# Expand_Board.net
KiCad netlist of a schematic drawn in Altium Designer
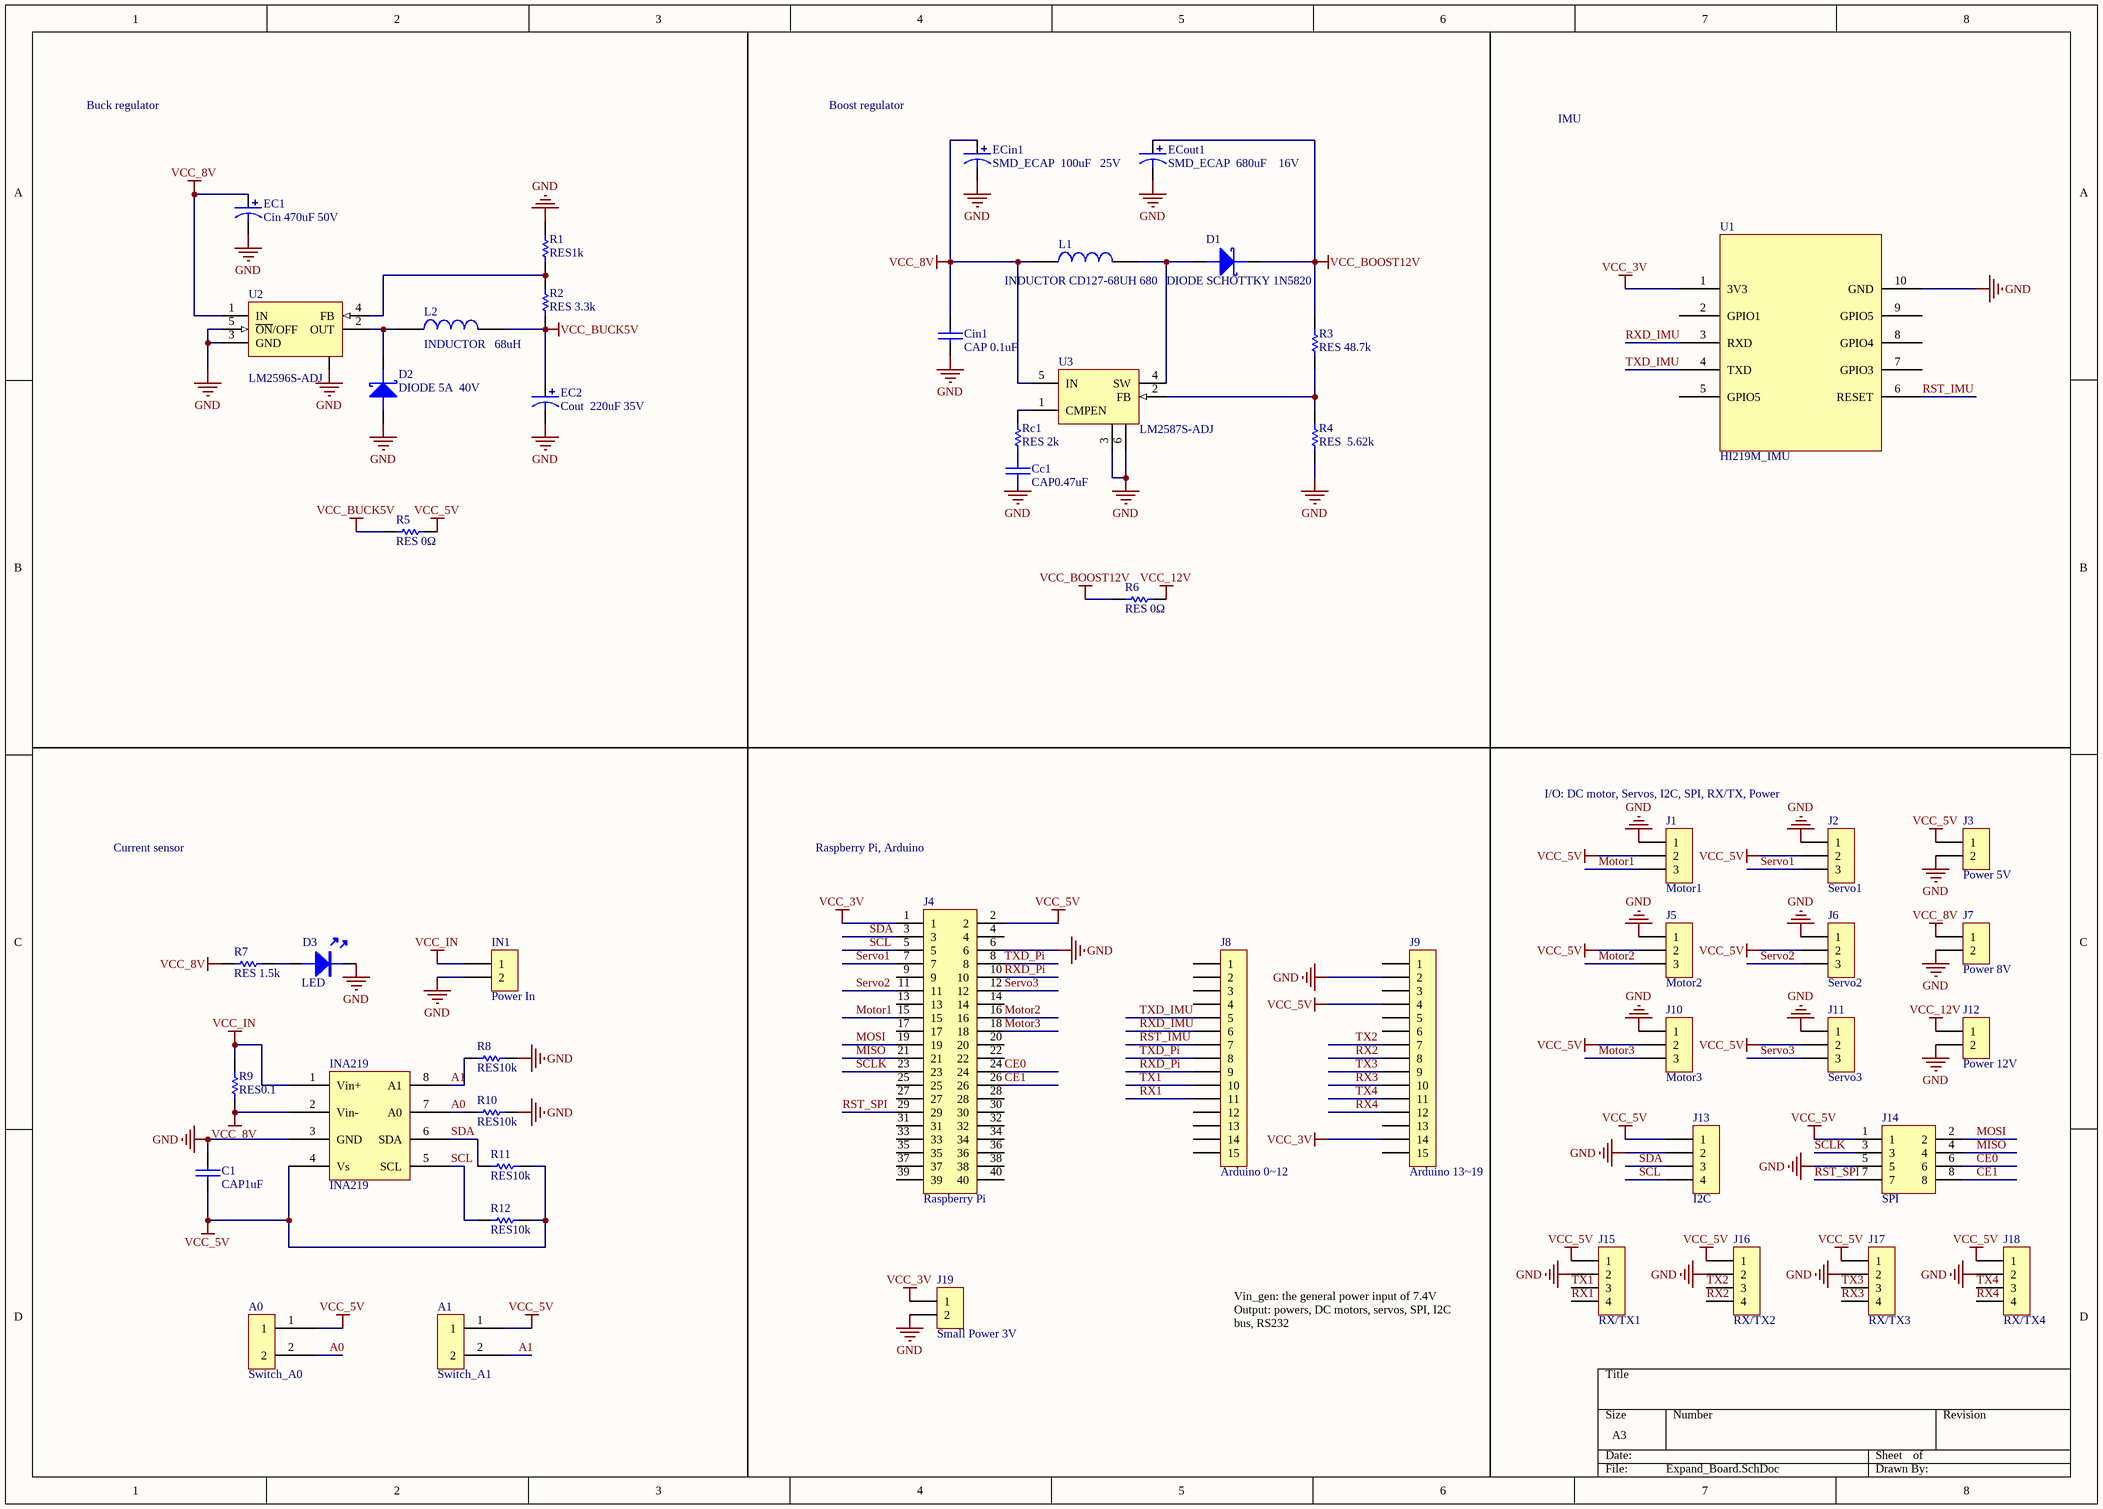
[diagram p0: Expand_Board.SchDoc]

(export (version "E")
  (design (tool "Eeschema 10.0.6"))
  (components
    (comp (ref "A0")
      (value "Switch_A0")
      (footprint "TSOP65P180X145-2N")
      (libsource (lib "Lianxin_Library") (part "Component_1"))
    )
    (comp (ref "A1")
      (value "Switch_A1")
      (footprint "TSOP65P180X145-2N")
      (libsource (lib "Lianxin_Library") (part "Component_1"))
    )
    (comp (ref "C1")
      (value "CAP1uF")
      (footprint "0603C")
      (description "无极性电容")
      (libsource (lib "电容") (part "CAP"))
    )
    (comp (ref "Cc1")
      (value "CAP0.47uF")
      (footprint "0805C")
      (description "无极性电容")
      (libsource (lib "电容") (part "CAP"))
    )
    (comp (ref "Cin1")
      (value "CAP 0.1uF")
      (footprint "0805C")
      (description "无极性电容")
      (libsource (lib "电容") (part "CAP"))
    )
    (comp (ref "D1")
      (value "DIODE SCHOTTKY 1N5820")
      (footprint "SMA/DO-214AC")
      (description "肖特基二极管")
      (libsource (lib "二极管") (part "DIODE SCHOTTKY"))
    )
    (comp (ref "D2")
      (value "DIODE 5A  40V")
      (footprint "SMA/DO-214AC")
      (description "肖特基二极管")
      (libsource (lib "二极管") (part "DIODE SCHOTTKY"))
    )
    (comp (ref "D3") (value "LED") (footprint "LED-0603B") (libsource (lib "LED") (part "LED")))
    (comp (ref "EC1")
      (value "Cin 470uF 50V")
      (footprint "SMD-EC8X8X10")
      (description "贴片电解电容")
      (libsource (lib "电容") (part "SMD_ECAP"))
    )
    (comp (ref "EC2")
      (value "Cout  220uF 35V")
      (footprint "SMD-EC8X8X10")
      (description "贴片电解电容")
      (libsource (lib "电容") (part "SMD_ECAP"))
    )
    (comp (ref "ECin1")
      (value "SMD_ECAP  100uF   25V")
      (footprint "SMD-EC8X8X10")
      (description "贴片电解电容")
      (libsource (lib "电容") (part "SMD_ECAP"))
    )
    (comp (ref "ECout1")
      (value "SMD_ECAP  680uF    16V")
      (footprint "SMD-EC8X8X10")
      (description "贴片电解电容")
      (libsource (lib "电容") (part "SMD_ECAP"))
    )
    (comp (ref "IN1")
      (value "Power In")
      (footprint "Pin HDR1X2/2.54mm-S")
      (libsource (lib "排针") (part "Pin HDR1X2"))
    )
    (comp (ref "INA219") (value "INA219") (footprint "INA219") (libsource (lib "INA219") (part "INA219")))
    (comp (ref "J1")
      (value "Motor1")
      (footprint "Pin HDR1X3/2.54mm-S")
      (libsource (lib "排针") (part "Pin HDR1X3"))
    )
    (comp (ref "J2")
      (value "Servo1")
      (footprint "Pin HDR1X3/2.54mm-S")
      (libsource (lib "排针") (part "Pin HDR1X3"))
    )
    (comp (ref "J3")
      (value "Power 5V")
      (footprint "Pin HDR1X2/2.54mm-S")
      (libsource (lib "排针") (part "Pin HDR1X2"))
    )
    (comp (ref "J4")
      (value "Raspberry Pi")
      (footprint "Pin HDR2X20/2.54mm-S")
      (libsource (lib "排针") (part "Pin HDR2X20"))
    )
    (comp (ref "J5")
      (value "Motor2")
      (footprint "Pin HDR1X3/2.54mm-S")
      (libsource (lib "排针") (part "Pin HDR1X3"))
    )
    (comp (ref "J6")
      (value "Servo2")
      (footprint "Pin HDR1X3/2.54mm-S")
      (libsource (lib "排针") (part "Pin HDR1X3"))
    )
    (comp (ref "J7")
      (value "Power 8V")
      (footprint "Pin HDR1X2/2.54mm-S")
      (libsource (lib "排针") (part "Pin HDR1X2"))
    )
    (comp (ref "J8")
      (value "Arduino 0~12")
      (footprint "Pin HDR1X15/2.54mm-S")
      (libsource (lib "排针") (part "Pin HDR1X15"))
    )
    (comp (ref "J9")
      (value "Arduino 13~19")
      (footprint "Pin HDR1X15/2.54mm-S")
      (libsource (lib "排针") (part "Pin HDR1X15"))
    )
    (comp (ref "J10")
      (value "Motor3")
      (footprint "Pin HDR1X3/2.54mm-S")
      (libsource (lib "排针") (part "Pin HDR1X3"))
    )
    (comp (ref "J11")
      (value "Servo3")
      (footprint "Pin HDR1X3/2.54mm-S")
      (libsource (lib "排针") (part "Pin HDR1X3"))
    )
    (comp (ref "J12")
      (value "Power 12V")
      (footprint "Pin HDR1X2/2.54mm-S")
      (libsource (lib "排针") (part "Pin HDR1X2"))
    )
    (comp (ref "J13")
      (value "I2C")
      (footprint "Pin HDR1X4/2.54mm-S")
      (libsource (lib "排针") (part "Pin HDR1X4"))
    )
    (comp (ref "J14")
      (value "SPI")
      (footprint "Pin HDR2X4/2.54mm-S")
      (libsource (lib "排针") (part "Pin HDR2X4"))
    )
    (comp (ref "J15")
      (value "RX/TX1")
      (footprint "Pin HDR1X4/2.54mm-S")
      (libsource (lib "排针") (part "Pin HDR1X4"))
    )
    (comp (ref "J16")
      (value "RX/TX2")
      (footprint "Pin HDR1X4/2.54mm-S")
      (libsource (lib "排针") (part "Pin HDR1X4"))
    )
    (comp (ref "J17")
      (value "RX/TX3")
      (footprint "Pin HDR1X4/2.54mm-S")
      (libsource (lib "排针") (part "Pin HDR1X4"))
    )
    (comp (ref "J18")
      (value "RX/TX4")
      (footprint "Pin HDR1X4/2.54mm-S")
      (libsource (lib "排针") (part "Pin HDR1X4"))
    )
    (comp (ref "J19")
      (value "Small Power 3V")
      (footprint "Pin HDR1X2/2.54mm-S")
      (libsource (lib "排针") (part "Pin HDR1X2"))
    )
    (comp (ref "L1")
      (value "INDUCTOR CD127-68UH 680")
      (footprint "CDRH127")
      (description "INDUCTOR")
      (libsource (lib "电感") (part "INDUCTOR"))
    )
    (comp (ref "L2")
      (value "INDUCTOR   68uH")
      (footprint "CDRH127")
      (description "INDUCTOR")
      (libsource (lib "电感") (part "INDUCTOR"))
    )
    (comp (ref "R1") (value "RES1k") (footprint "0603R") (libsource (lib "电阻") (part "RES")))
    (comp (ref "R2") (value "RES 3.3k") (footprint "0603R") (libsource (lib "电阻") (part "RES")))
    (comp (ref "R3") (value "RES 48.7k") (footprint "0603R") (libsource (lib "电阻") (part "RES")))
    (comp (ref "R4") (value "RES  5.62k") (footprint "0603R") (libsource (lib "电阻") (part "RES")))
    (comp (ref "R5") (value "RES 0Ω") (footprint "0603R") (libsource (lib "电阻") (part "RES")))
    (comp (ref "R6") (value "RES 0Ω") (footprint "0603R") (libsource (lib "电阻") (part "RES")))
    (comp (ref "R7") (value "RES 1.5k") (footprint "0603R") (libsource (lib "电阻") (part "RES")))
    (comp (ref "R8") (value "RES10k") (footprint "0603R") (libsource (lib "电阻") (part "RES")))
    (comp (ref "R9") (value "RES0.1") (footprint "2512R") (libsource (lib "电阻") (part "RES")))
    (comp (ref "R10") (value "RES10k") (footprint "0603R") (libsource (lib "电阻") (part "RES")))
    (comp (ref "R11") (value "RES10k") (footprint "0603R") (libsource (lib "电阻") (part "RES")))
    (comp (ref "R12") (value "RES10k") (footprint "0603R") (libsource (lib "电阻") (part "RES")))
    (comp (ref "Rc1") (value "RES 2k") (footprint "0603R") (libsource (lib "电阻") (part "RES")))
    (comp (ref "U1")
      (value "HI219M_IMU")
      (footprint "SON127P1220X265-10N")
      (libsource (lib "Hi219M_IMU_Lib") (part "Component_1"))
    )
    (comp (ref "U2")
      (value "LM2596S-ADJ")
      (footprint "TO-263-5")
      (description "可调稳压芯片")
      (fields (field (name "PUBLISHER") "Altium Limited"))
      (libsource (lib "fszhang") (part "LM2596S-ADJ"))
    )
    (comp (ref "U3")
      (value "LM2587S-ADJ")
      (footprint "TO-263-5")
      (description "DC升压")
      (fields (field (name "PUBLISHER") "Altium Limited"))
      (libsource (lib "fszhang") (part "LM2577S-ADJ"))
    )
  )
  (nets
    (net (code "1") (name "/A0") (class "Default")
      (node (ref "A0") (pin "2") (pinfunction "2_2") (pintype "passive"))
      (node (ref "INA219") (pin "7") (pinfunction "A0_7") (pintype "passive"))
      (node (ref "R10") (pin "1") (pinfunction "1_1") (pintype "passive"))
    )
    (net (code "2") (name "/A1") (class "Default")
      (node (ref "A1") (pin "2") (pinfunction "2_2") (pintype "passive"))
      (node (ref "INA219") (pin "8") (pinfunction "A1_8") (pintype "passive"))
      (node (ref "R8") (pin "1") (pinfunction "1_1") (pintype "passive"))
    )
    (net (code "3") (name "/CE0") (class "Default")
      (node (ref "J14") (pin "6") (pinfunction "6_6") (pintype "passive"))
      (node (ref "J4") (pin "24") (pinfunction "24_24") (pintype "passive"))
    )
    (net (code "4") (name "/CE1") (class "Default")
      (node (ref "J14") (pin "8") (pinfunction "8_8") (pintype "passive"))
      (node (ref "J4") (pin "26") (pinfunction "26_26") (pintype "passive"))
    )
    (net (code "5") (name "/MISO") (class "Default")
      (node (ref "J14") (pin "4") (pinfunction "4_4") (pintype "passive"))
      (node (ref "J4") (pin "21") (pinfunction "21_21") (pintype "passive"))
    )
    (net (code "6") (name "/MOSI") (class "Default")
      (node (ref "J14") (pin "2") (pinfunction "2_2") (pintype "passive"))
      (node (ref "J4") (pin "19") (pinfunction "19_19") (pintype "passive"))
    )
    (net (code "7") (name "/Motor1") (class "Default")
      (node (ref "J1") (pin "3") (pinfunction "3_3") (pintype "passive"))
      (node (ref "J4") (pin "15") (pinfunction "15_15") (pintype "passive"))
    )
    (net (code "8") (name "/Motor2") (class "Default")
      (node (ref "J4") (pin "16") (pinfunction "16_16") (pintype "passive"))
      (node (ref "J5") (pin "3") (pinfunction "3_3") (pintype "passive"))
    )
    (net (code "9") (name "/Motor3") (class "Default")
      (node (ref "J10") (pin "3") (pinfunction "3_3") (pintype "passive"))
      (node (ref "J4") (pin "18") (pinfunction "18_18") (pintype "passive"))
    )
    (net (code "10") (name "/RST_IMU") (class "Default")
      (node (ref "J8") (pin "7") (pinfunction "7_7") (pintype "passive"))
      (node (ref "U1") (pin "6") (pinfunction "RESET_6") (pintype "passive"))
    )
    (net (code "11") (name "/RST_SPI") (class "Default")
      (node (ref "J14") (pin "7") (pinfunction "7_7") (pintype "passive"))
      (node (ref "J4") (pin "29") (pinfunction "29_29") (pintype "passive"))
    )
    (net (code "12") (name "/RX1") (class "Default")
      (node (ref "J15") (pin "4") (pinfunction "4_4") (pintype "passive"))
      (node (ref "J8") (pin "11") (pinfunction "11_11") (pintype "passive"))
    )
    (net (code "13") (name "/RX2") (class "Default")
      (node (ref "J16") (pin "4") (pinfunction "4_4") (pintype "passive"))
      (node (ref "J9") (pin "8") (pinfunction "8_8") (pintype "passive"))
    )
    (net (code "14") (name "/RX3") (class "Default")
      (node (ref "J17") (pin "4") (pinfunction "4_4") (pintype "passive"))
      (node (ref "J9") (pin "10") (pinfunction "10_10") (pintype "passive"))
    )
    (net (code "15") (name "/RX4") (class "Default")
      (node (ref "J18") (pin "4") (pinfunction "4_4") (pintype "passive"))
      (node (ref "J9") (pin "12") (pinfunction "12_12") (pintype "passive"))
    )
    (net (code "16") (name "/RXD_IMU") (class "Default")
      (node (ref "J8") (pin "6") (pinfunction "6_6") (pintype "passive"))
      (node (ref "U1") (pin "3") (pinfunction "RXD_3") (pintype "passive"))
    )
    (net (code "17") (name "/RXD_Pi") (class "Default")
      (node (ref "J4") (pin "10") (pinfunction "10_10") (pintype "passive"))
      (node (ref "J8") (pin "9") (pinfunction "9_9") (pintype "passive"))
    )
    (net (code "18") (name "/SCL") (class "Default")
      (node (ref "INA219") (pin "5") (pinfunction "SCL_5") (pintype "passive"))
      (node (ref "J13") (pin "4") (pinfunction "4_4") (pintype "passive"))
      (node (ref "J4") (pin "5") (pinfunction "5_5") (pintype "passive"))
      (node (ref "R12") (pin "1") (pinfunction "1_1") (pintype "passive"))
    )
    (net (code "19") (name "/SCLK") (class "Default")
      (node (ref "J14") (pin "3") (pinfunction "3_3") (pintype "passive"))
      (node (ref "J4") (pin "23") (pinfunction "23_23") (pintype "passive"))
    )
    (net (code "20") (name "/SDA") (class "Default")
      (node (ref "INA219") (pin "6") (pinfunction "SDA_6") (pintype "passive"))
      (node (ref "J13") (pin "3") (pinfunction "3_3") (pintype "passive"))
      (node (ref "J4") (pin "3") (pinfunction "3_3") (pintype "passive"))
      (node (ref "R11") (pin "1") (pinfunction "1_1") (pintype "passive"))
    )
    (net (code "21") (name "/Servo1") (class "Default")
      (node (ref "J2") (pin "3") (pinfunction "3_3") (pintype "passive"))
      (node (ref "J4") (pin "7") (pinfunction "7_7") (pintype "passive"))
    )
    (net (code "22") (name "/Servo2") (class "Default")
      (node (ref "J4") (pin "11") (pinfunction "11_11") (pintype "passive"))
      (node (ref "J6") (pin "3") (pinfunction "3_3") (pintype "passive"))
    )
    (net (code "23") (name "/Servo3") (class "Default")
      (node (ref "J11") (pin "3") (pinfunction "3_3") (pintype "passive"))
      (node (ref "J4") (pin "12") (pinfunction "12_12") (pintype "passive"))
    )
    (net (code "24") (name "/TX1") (class "Default")
      (node (ref "J15") (pin "3") (pinfunction "3_3") (pintype "passive"))
      (node (ref "J8") (pin "10") (pinfunction "10_10") (pintype "passive"))
    )
    (net (code "25") (name "/TX2") (class "Default")
      (node (ref "J16") (pin "3") (pinfunction "3_3") (pintype "passive"))
      (node (ref "J9") (pin "7") (pinfunction "7_7") (pintype "passive"))
    )
    (net (code "26") (name "/TX3") (class "Default")
      (node (ref "J17") (pin "3") (pinfunction "3_3") (pintype "passive"))
      (node (ref "J9") (pin "9") (pinfunction "9_9") (pintype "passive"))
    )
    (net (code "27") (name "/TX4") (class "Default")
      (node (ref "J18") (pin "3") (pinfunction "3_3") (pintype "passive"))
      (node (ref "J9") (pin "11") (pinfunction "11_11") (pintype "passive"))
    )
    (net (code "28") (name "/TXD_IMU") (class "Default")
      (node (ref "J8") (pin "5") (pinfunction "5_5") (pintype "passive"))
      (node (ref "U1") (pin "4") (pinfunction "TXD_4") (pintype "passive"))
    )
    (net (code "29") (name "/TXD_Pi") (class "Default")
      (node (ref "J4") (pin "8") (pinfunction "8_8") (pintype "passive"))
      (node (ref "J8") (pin "8") (pinfunction "8_8") (pintype "passive"))
    )
    (net (code "30") (name "GND") (class "Default")
      (node (ref "C1") (pin "2") (pinfunction "2_2") (pintype "passive"))
      (node (ref "Cc1") (pin "1") (pinfunction "1_1") (pintype "passive"))
      (node (ref "Cin1") (pin "1") (pinfunction "1_1") (pintype "passive"))
      (node (ref "D2") (pin "A") (pinfunction "A_A") (pintype "passive"))
      (node (ref "D3") (pin "K") (pinfunction "K_K") (pintype "passive"))
      (node (ref "EC1") (pin "2") (pinfunction "2_2") (pintype "passive"))
      (node (ref "EC2") (pin "2") (pinfunction "2_2") (pintype "passive"))
      (node (ref "ECin1") (pin "2") (pinfunction "2_2") (pintype "passive"))
      (node (ref "ECout1") (pin "2") (pinfunction "2_2") (pintype "passive"))
      (node (ref "IN1") (pin "2") (pinfunction "2_2") (pintype "passive"))
      (node (ref "INA219") (pin "3") (pinfunction "GND_3") (pintype "passive"))
      (node (ref "J1") (pin "1") (pinfunction "1_1") (pintype "passive"))
      (node (ref "J10") (pin "1") (pinfunction "1_1") (pintype "passive"))
      (node (ref "J11") (pin "1") (pinfunction "1_1") (pintype "passive"))
      (node (ref "J12") (pin "2") (pinfunction "2_2") (pintype "passive"))
      (node (ref "J13") (pin "2") (pinfunction "2_2") (pintype "passive"))
      (node (ref "J14") (pin "5") (pinfunction "5_5") (pintype "passive"))
      (node (ref "J15") (pin "2") (pinfunction "2_2") (pintype "passive"))
      (node (ref "J16") (pin "2") (pinfunction "2_2") (pintype "passive"))
      (node (ref "J17") (pin "2") (pinfunction "2_2") (pintype "passive"))
      (node (ref "J18") (pin "2") (pinfunction "2_2") (pintype "passive"))
      (node (ref "J19") (pin "2") (pinfunction "2_2") (pintype "passive"))
      (node (ref "J2") (pin "1") (pinfunction "1_1") (pintype "passive"))
      (node (ref "J3") (pin "2") (pinfunction "2_2") (pintype "passive"))
      (node (ref "J4") (pin "6") (pinfunction "6_6") (pintype "passive"))
      (node (ref "J5") (pin "1") (pinfunction "1_1") (pintype "passive"))
      (node (ref "J6") (pin "1") (pinfunction "1_1") (pintype "passive"))
      (node (ref "J7") (pin "2") (pinfunction "2_2") (pintype "passive"))
      (node (ref "J9") (pin "2") (pinfunction "2_2") (pintype "passive"))
      (node (ref "R1") (pin "2") (pinfunction "2_2") (pintype "passive"))
      (node (ref "R10") (pin "2") (pinfunction "2_2") (pintype "passive"))
      (node (ref "R4") (pin "1") (pinfunction "1_1") (pintype "passive"))
      (node (ref "R8") (pin "2") (pinfunction "2_2") (pintype "passive"))
      (node (ref "U1") (pin "10") (pinfunction "GND_10") (pintype "passive"))
      (node (ref "U2") (pin "3") (pinfunction "GND_3") (pintype "power_in"))
      (node (ref "U2") (pin "5") (pinfunction "~{ON}/OFF_5") (pintype "input"))
      (node (ref "U2") (pin "6") (pinfunction "6_6") (pintype "power_in"))
      (node (ref "U3") (pin "3") (pinfunction "GND_3") (pintype "power_in"))
      (node (ref "U3") (pin "6") (pinfunction "6_6") (pintype "passive"))
    )
    (net (code "31") (name "Net-(Cc1-Pad2)") (class "Default")
      (node (ref "Cc1") (pin "2") (pinfunction "2_2") (pintype "passive"))
      (node (ref "Rc1") (pin "1") (pinfunction "1_1") (pintype "passive"))
    )
    (net (code "32") (name "Net-(D3-PadA)") (class "Default")
      (node (ref "D3") (pin "A") (pinfunction "A_A") (pintype "passive"))
      (node (ref "R7") (pin "1") (pinfunction "1_1") (pintype "passive"))
    )
    (net (code "33") (name "Net-(U2-FB)") (class "Default")
      (node (ref "R1") (pin "1") (pinfunction "1_1") (pintype "passive"))
      (node (ref "R2") (pin "2") (pinfunction "2_2") (pintype "passive"))
      (node (ref "U2") (pin "4") (pinfunction "FB_4") (pintype "input"))
    )
    (net (code "34") (name "Net-(U2-OUT)") (class "Default")
      (node (ref "D2") (pin "K") (pinfunction "K_K") (pintype "passive"))
      (node (ref "L2") (pin "1") (pinfunction "1_1") (pintype "passive"))
      (node (ref "U2") (pin "2") (pinfunction "OUT_2") (pintype "power_in"))
    )
    (net (code "35") (name "Net-(U3-CMPEN)") (class "Default")
      (node (ref "Rc1") (pin "2") (pinfunction "2_2") (pintype "passive"))
      (node (ref "U3") (pin "1") (pinfunction "CMPEN_1") (pintype "passive"))
    )
    (net (code "36") (name "Net-(U3-FB)") (class "Default")
      (node (ref "R3") (pin "1") (pinfunction "1_1") (pintype "passive"))
      (node (ref "R4") (pin "2") (pinfunction "2_2") (pintype "passive"))
      (node (ref "U3") (pin "2") (pinfunction "FB_2") (pintype "input"))
    )
    (net (code "37") (name "Net-(U3-SW)") (class "Default")
      (node (ref "D1") (pin "A") (pinfunction "A_A") (pintype "passive"))
      (node (ref "L1") (pin "2") (pinfunction "2_2") (pintype "passive"))
      (node (ref "U3") (pin "4") (pinfunction "SW_4") (pintype "power_in"))
    )
    (net (code "38") (name "VCC_3V") (class "Default")
      (node (ref "J19") (pin "1") (pinfunction "1_1") (pintype "passive"))
      (node (ref "J4") (pin "1") (pinfunction "1_1") (pintype "passive"))
      (node (ref "J9") (pin "14") (pinfunction "14_14") (pintype "passive"))
      (node (ref "U1") (pin "1") (pinfunction "3V3_1") (pintype "passive"))
    )
    (net (code "39") (name "VCC_5V") (class "Default")
      (node (ref "A0") (pin "1") (pinfunction "1_1") (pintype "passive"))
      (node (ref "A1") (pin "1") (pinfunction "1_1") (pintype "passive"))
      (node (ref "C1") (pin "1") (pinfunction "1_1") (pintype "passive"))
      (node (ref "INA219") (pin "4") (pinfunction "Vs_4") (pintype "passive"))
      (node (ref "J1") (pin "2") (pinfunction "2_2") (pintype "passive"))
      (node (ref "J10") (pin "2") (pinfunction "2_2") (pintype "passive"))
      (node (ref "J11") (pin "2") (pinfunction "2_2") (pintype "passive"))
      (node (ref "J13") (pin "1") (pinfunction "1_1") (pintype "passive"))
      (node (ref "J14") (pin "1") (pinfunction "1_1") (pintype "passive"))
      (node (ref "J15") (pin "1") (pinfunction "1_1") (pintype "passive"))
      (node (ref "J16") (pin "1") (pinfunction "1_1") (pintype "passive"))
      (node (ref "J17") (pin "1") (pinfunction "1_1") (pintype "passive"))
      (node (ref "J18") (pin "1") (pinfunction "1_1") (pintype "passive"))
      (node (ref "J2") (pin "2") (pinfunction "2_2") (pintype "passive"))
      (node (ref "J3") (pin "1") (pinfunction "1_1") (pintype "passive"))
      (node (ref "J4") (pin "2") (pinfunction "2_2") (pintype "passive"))
      (node (ref "J5") (pin "2") (pinfunction "2_2") (pintype "passive"))
      (node (ref "J6") (pin "2") (pinfunction "2_2") (pintype "passive"))
      (node (ref "J9") (pin "4") (pinfunction "4_4") (pintype "passive"))
      (node (ref "R11") (pin "2") (pinfunction "2_2") (pintype "passive"))
      (node (ref "R12") (pin "2") (pinfunction "2_2") (pintype "passive"))
      (node (ref "R5") (pin "2") (pinfunction "2_2") (pintype "passive"))
    )
    (net (code "40") (name "VCC_8V") (class "Default")
      (node (ref "Cin1") (pin "2") (pinfunction "2_2") (pintype "passive"))
      (node (ref "EC1") (pin "1") (pinfunction "1_1") (pintype "passive"))
      (node (ref "ECin1") (pin "1") (pinfunction "1_1") (pintype "passive"))
      (node (ref "INA219") (pin "2") (pinfunction "Vin-_2") (pintype "passive"))
      (node (ref "J7") (pin "1") (pinfunction "1_1") (pintype "passive"))
      (node (ref "L1") (pin "1") (pinfunction "1_1") (pintype "passive"))
      (node (ref "R7") (pin "2") (pinfunction "2_2") (pintype "passive"))
      (node (ref "R9") (pin "2") (pinfunction "2_2") (pintype "passive"))
      (node (ref "U2") (pin "1") (pinfunction "IN_1") (pintype "power_in"))
      (node (ref "U3") (pin "5") (pinfunction "IN_5") (pintype "power_in"))
    )
    (net (code "41") (name "VCC_12V") (class "Default")
      (node (ref "J12") (pin "1") (pinfunction "1_1") (pintype "passive"))
      (node (ref "R6") (pin "2") (pinfunction "2_2") (pintype "passive"))
    )
    (net (code "42") (name "VCC_BOOST12V") (class "Default")
      (node (ref "D1") (pin "K") (pinfunction "K_K") (pintype "passive"))
      (node (ref "ECout1") (pin "1") (pinfunction "1_1") (pintype "passive"))
      (node (ref "R3") (pin "2") (pinfunction "2_2") (pintype "passive"))
      (node (ref "R6") (pin "1") (pinfunction "1_1") (pintype "passive"))
    )
    (net (code "43") (name "VCC_BUCK5V") (class "Default")
      (node (ref "EC2") (pin "1") (pinfunction "1_1") (pintype "passive"))
      (node (ref "L2") (pin "2") (pinfunction "2_2") (pintype "passive"))
      (node (ref "R2") (pin "1") (pinfunction "1_1") (pintype "passive"))
      (node (ref "R5") (pin "1") (pinfunction "1_1") (pintype "passive"))
    )
    (net (code "44") (name "VCC_IN") (class "Default")
      (node (ref "IN1") (pin "1") (pinfunction "1_1") (pintype "passive"))
      (node (ref "INA219") (pin "1") (pinfunction "Vin+_1") (pintype "passive"))
      (node (ref "R9") (pin "1") (pinfunction "1_1") (pintype "passive"))
    )
    (net (code "45") (name "unconnected-(J4-Pad4)") (class "Default")
      (node (ref "J4") (pin "4") (pinfunction "4_4") (pintype "passive"))
    )
    (net (code "46") (name "unconnected-(J4-Pad9)") (class "Default")
      (node (ref "J4") (pin "9") (pinfunction "9_9") (pintype "passive"))
    )
    (net (code "47") (name "unconnected-(J4-Pad13)") (class "Default")
      (node (ref "J4") (pin "13") (pinfunction "13_13") (pintype "passive"))
    )
    (net (code "48") (name "unconnected-(J4-Pad14)") (class "Default")
      (node (ref "J4") (pin "14") (pinfunction "14_14") (pintype "passive"))
    )
    (net (code "49") (name "unconnected-(J4-Pad17)") (class "Default")
      (node (ref "J4") (pin "17") (pinfunction "17_17") (pintype "passive"))
    )
    (net (code "50") (name "unconnected-(J4-Pad20)") (class "Default")
      (node (ref "J4") (pin "20") (pinfunction "20_20") (pintype "passive"))
    )
    (net (code "51") (name "unconnected-(J4-Pad22)") (class "Default")
      (node (ref "J4") (pin "22") (pinfunction "22_22") (pintype "passive"))
    )
    (net (code "52") (name "unconnected-(J4-Pad25)") (class "Default")
      (node (ref "J4") (pin "25") (pinfunction "25_25") (pintype "passive"))
    )
    (net (code "53") (name "unconnected-(J4-Pad27)") (class "Default")
      (node (ref "J4") (pin "27") (pinfunction "27_27") (pintype "passive"))
    )
    (net (code "54") (name "unconnected-(J4-Pad28)") (class "Default")
      (node (ref "J4") (pin "28") (pinfunction "28_28") (pintype "passive"))
    )
    (net (code "55") (name "unconnected-(J4-Pad30)") (class "Default")
      (node (ref "J4") (pin "30") (pinfunction "30_30") (pintype "passive"))
    )
    (net (code "56") (name "unconnected-(J4-Pad31)") (class "Default")
      (node (ref "J4") (pin "31") (pinfunction "31_31") (pintype "passive"))
    )
    (net (code "57") (name "unconnected-(J4-Pad32)") (class "Default")
      (node (ref "J4") (pin "32") (pinfunction "32_32") (pintype "passive"))
    )
    (net (code "58") (name "unconnected-(J4-Pad33)") (class "Default")
      (node (ref "J4") (pin "33") (pinfunction "33_33") (pintype "passive"))
    )
    (net (code "59") (name "unconnected-(J4-Pad34)") (class "Default")
      (node (ref "J4") (pin "34") (pinfunction "34_34") (pintype "passive"))
    )
    (net (code "60") (name "unconnected-(J4-Pad35)") (class "Default")
      (node (ref "J4") (pin "35") (pinfunction "35_35") (pintype "passive"))
    )
    (net (code "61") (name "unconnected-(J4-Pad36)") (class "Default")
      (node (ref "J4") (pin "36") (pinfunction "36_36") (pintype "passive"))
    )
    (net (code "62") (name "unconnected-(J4-Pad37)") (class "Default")
      (node (ref "J4") (pin "37") (pinfunction "37_37") (pintype "passive"))
    )
    (net (code "63") (name "unconnected-(J4-Pad38)") (class "Default")
      (node (ref "J4") (pin "38") (pinfunction "38_38") (pintype "passive"))
    )
    (net (code "64") (name "unconnected-(J4-Pad39)") (class "Default")
      (node (ref "J4") (pin "39") (pinfunction "39_39") (pintype "passive"))
    )
    (net (code "65") (name "unconnected-(J4-Pad40)") (class "Default")
      (node (ref "J4") (pin "40") (pinfunction "40_40") (pintype "passive"))
    )
    (net (code "66") (name "unconnected-(J8-Pad1)") (class "Default")
      (node (ref "J8") (pin "1") (pinfunction "1_1") (pintype "passive"))
    )
    (net (code "67") (name "unconnected-(J8-Pad2)") (class "Default")
      (node (ref "J8") (pin "2") (pinfunction "2_2") (pintype "passive"))
    )
    (net (code "68") (name "unconnected-(J8-Pad3)") (class "Default")
      (node (ref "J8") (pin "3") (pinfunction "3_3") (pintype "passive"))
    )
    (net (code "69") (name "unconnected-(J8-Pad4)") (class "Default")
      (node (ref "J8") (pin "4") (pinfunction "4_4") (pintype "passive"))
    )
    (net (code "70") (name "unconnected-(J8-Pad12)") (class "Default")
      (node (ref "J8") (pin "12") (pinfunction "12_12") (pintype "passive"))
    )
    (net (code "71") (name "unconnected-(J8-Pad13)") (class "Default")
      (node (ref "J8") (pin "13") (pinfunction "13_13") (pintype "passive"))
    )
    (net (code "72") (name "unconnected-(J8-Pad14)") (class "Default")
      (node (ref "J8") (pin "14") (pinfunction "14_14") (pintype "passive"))
    )
    (net (code "73") (name "unconnected-(J8-Pad15)") (class "Default")
      (node (ref "J8") (pin "15") (pinfunction "15_15") (pintype "passive"))
    )
    (net (code "74") (name "unconnected-(J9-Pad1)") (class "Default")
      (node (ref "J9") (pin "1") (pinfunction "1_1") (pintype "passive"))
    )
    (net (code "75") (name "unconnected-(J9-Pad3)") (class "Default")
      (node (ref "J9") (pin "3") (pinfunction "3_3") (pintype "passive"))
    )
    (net (code "76") (name "unconnected-(J9-Pad5)") (class "Default")
      (node (ref "J9") (pin "5") (pinfunction "5_5") (pintype "passive"))
    )
    (net (code "77") (name "unconnected-(J9-Pad6)") (class "Default")
      (node (ref "J9") (pin "6") (pinfunction "6_6") (pintype "passive"))
    )
    (net (code "78") (name "unconnected-(J9-Pad13)") (class "Default")
      (node (ref "J9") (pin "13") (pinfunction "13_13") (pintype "passive"))
    )
    (net (code "79") (name "unconnected-(J9-Pad15)") (class "Default")
      (node (ref "J9") (pin "15") (pinfunction "15_15") (pintype "passive"))
    )
    (net (code "80") (name "unconnected-(U1-GPIO1-Pad2)") (class "Default")
      (node (ref "U1") (pin "2") (pinfunction "GPIO1_2") (pintype "passive"))
    )
    (net (code "81") (name "unconnected-(U1-GPIO3-Pad7)") (class "Default")
      (node (ref "U1") (pin "7") (pinfunction "GPIO3_7") (pintype "passive"))
    )
    (net (code "82") (name "unconnected-(U1-GPIO4-Pad8)") (class "Default")
      (node (ref "U1") (pin "8") (pinfunction "GPIO4_8") (pintype "passive"))
    )
    (net (code "83") (name "unconnected-(U1-GPIO5-Pad5)") (class "Default")
      (node (ref "U1") (pin "5") (pinfunction "GPIO5_5") (pintype "passive"))
    )
    (net (code "84") (name "unconnected-(U1-GPIO5-Pad9)") (class "Default")
      (node (ref "U1") (pin "9") (pinfunction "GPIO5_9") (pintype "passive"))
    )
  )
)
